# PowerManagement.net
KiCad netlist of a schematic drawn in Altium Designer
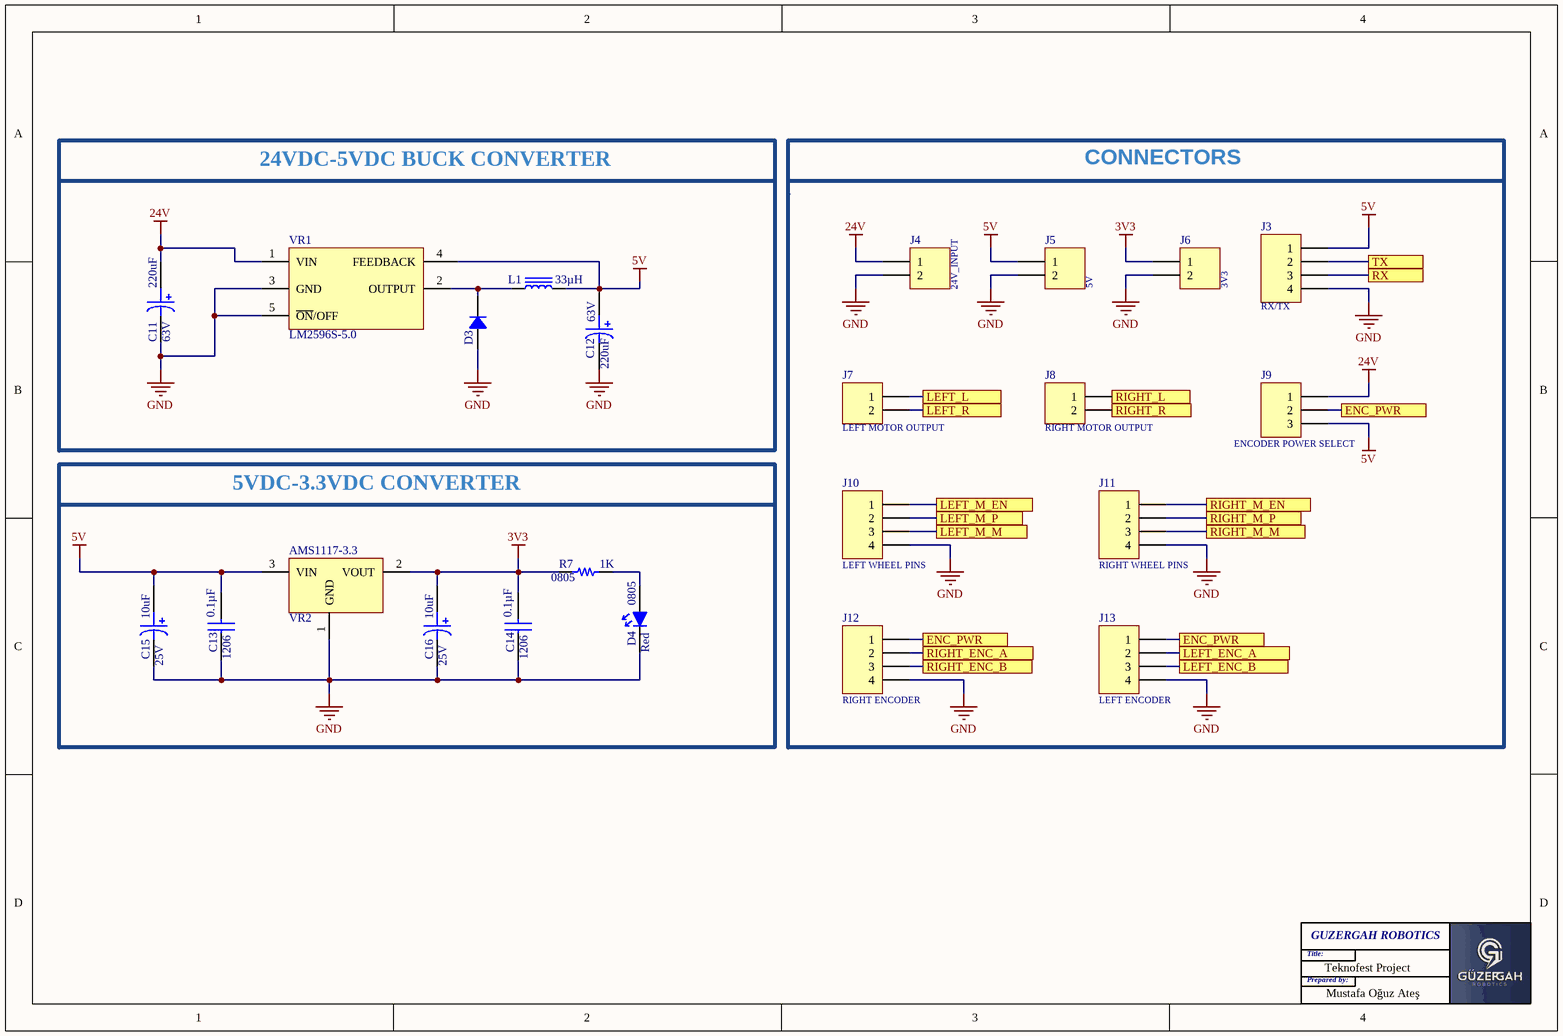
[diagram p0: PowerManagement.SchDoc]

(export (version "E")
  (design (tool "Eeschema 10.0.6"))
  (components
    (comp (ref "C11")
      (value "220uF")
      (footprint "CAP_ALUM_220uF_10x16 5MM")
      (description "CAP.EL.220uF 63V 10x16 5MM 105C")
      (fields (field (name "VOLTAGE - RATED") "63V") (field (name "Comment") "RD1J227M10016PA100"))
      (libsource (lib "TeknoFest") (part "CAP_ALUM_220uF_TH"))
    )
    (comp (ref "C12")
      (value "220uF")
      (footprint "CAP_ALUM_220uF_10x16 5MM")
      (description "CAP.EL.220uF 63V 10x16 5MM 105C")
      (fields (field (name "VOLTAGE - RATED") "63V") (field (name "Comment") "RD1J227M10016PA100"))
      (libsource (lib "TeknoFest") (part "CAP_ALUM_220uF_TH"))
    )
    (comp (ref "C13")
      (value "0.1µF")
      (footprint "CAP_1206_0.1uF")
      (description "CAP CER 0.1 uF 1206")
      (fields (field (name "PACKAGE / CASE") "1206") (field (name "Comment") "CAP_1206_0.1uF"))
      (libsource (lib "TeknoFest") (part "CAP_1206_0.1uF"))
    )
    (comp (ref "C14")
      (value "0.1µF")
      (footprint "CAP_1206_0.1uF")
      (description "CAP CER 0.1 uF 1206")
      (fields (field (name "PACKAGE / CASE") "1206") (field (name "Comment") "CAP_1206_0.1uF"))
      (libsource (lib "TeknoFest") (part "CAP_1206_0.1uF"))
    )
    (comp (ref "C15")
      (value "10uF")
      (footprint "CAP_ALUM_10uF_TH")
      (description "CAP.EL.10uF 25V 4x7 1.5MM 105C BULK KOSHIN")
      (fields (field (name "VOLTAGE - RATED") "25V") (field (name "Comment") "PKRJ-025V100MB070"))
      (libsource (lib "TeknoFest") (part "CAP_ALUM_10uF_TH"))
    )
    (comp (ref "C16")
      (value "10uF")
      (footprint "CAP_ALUM_10uF_TH")
      (description "CAP.EL.10uF 25V 4x7 1.5MM 105C BULK KOSHIN")
      (fields (field (name "VOLTAGE - RATED") "25V") (field (name "Comment") "PKRJ-025V100MB070"))
      (libsource (lib "TeknoFest") (part "CAP_ALUM_10uF_TH"))
    )
    (comp (ref "D3")
      (value "SK56-HT")
      (footprint "DIODE SCHOTTKY")
      (description "5A 60V DO214AB SMC")
      (libsource (lib "TeknoFest") (part "DIODE SCHOTTKY"))
    )
    (comp (ref "D4")
      (value "LED RED 0805")
      (footprint "LED_RED_0805")
      (description "KOMPONENT SEÇİLMEDİ")
      (fields
        (field (name "MANUFACTURER") "Osram Opto")
        (field (name "MANUFACTURER PART NUMBER") "LH R974-LP-1")
        (field (name "PACKAGE / CASE") "0805")
        (field (name "COLOR") "Red")
        (field (name "DESIGNED BY") "Mustafa")
      )
      (libsource (lib "TeknoFest") (part "LED RED 0805"))
    )
    (comp (ref "J3")
      (value "DS1023-1X4S21")
      (footprint "RX/TX HEADER")
      (description "FEMALE HEADER 4PIN(1x4) 2.54mm THT V/T TRAY")
      (libsource (lib "TeknoFest") (part "RX/TX HEADER"))
    )
    (comp (ref "J4")
      (value "DG381S-3.81-02P-14-00AH")
      (footprint "24V_IN KONNEKTÖR")
      (description "TERM.BLK.3.81MM 2P PCB TYPE GREEN")
      (libsource (lib "TeknoFest") (part "24V_IN"))
    )
    (comp (ref "J5")
      (value "L-KLS1-208-1-02-S")
      (footprint "5V JUMPER")
      (description "FEMALE HEADER 2PIN(1x2) 2.54mm THT V/T TRAY")
      (libsource (lib "TeknoFest") (part "5V_JUMPER_HEADER"))
    )
    (comp (ref "J6")
      (value "L-KLS1-208-1-02-S")
      (footprint "3V3 JUMPER")
      (description "FEMALE HEADER 2PIN(1x2) 2.54mm THT V/T TRAY")
      (libsource (lib "TeknoFest") (part "3V3_JUMPER_HEADER"))
    )
    (comp (ref "J7")
      (value "DG381S-3.81-02P-14-00AH")
      (footprint "LEFT MOTOR OUTPUT CONNECTOR")
      (description "DG381S-3.81-02P-14-00AH - TERM.BLK.3.81MM 2P PCB TYPE GREEN")
      (libsource (lib "TeknoFest") (part "LEFT MOTOR OUTPUT"))
    )
    (comp (ref "J8")
      (value "DG381S-3.81-02P-14-00AH")
      (footprint "RIGHT MOTOR OUTPUT CONNECTOR")
      (description "DG381S-3.81-02P-14-00AH - TERM.BLK.3.81MM 2P PCB TYPE GREEN")
      (libsource (lib "TeknoFest") (part "RIGHT MOTOR OUTPUT"))
    )
    (comp (ref "J9")
      (value "DS1023-1X3S21")
      (footprint "ENCODER POWER SELECT.1")
      (description "FEMALE HEADER 3PIN(1x3) 2.54mm THT V/T")
      (libsource (lib "TeknoFest") (part "ENCODER POWER SELECT"))
    )
    (comp (ref "J10")
      (value "DS1023-1X4S21")
      (footprint "LEFT WHEEL PINS")
      (description "FEMALE HEADER 4PIN(1x4) 2.54mm THT V/T TRAY")
      (libsource (lib "TeknoFest") (part "LEFT WHEEL PINS"))
    )
    (comp (ref "J11")
      (value "DS1023-1X4S21")
      (footprint "RIGHT WHEEL PINS")
      (description "DS1023-1X4S21 - FEMALE HEADER 4PIN(1x4) 2.54mm THT V/T TRAY")
      (libsource (lib "TeknoFest") (part "RIGHT WHEEL PINS"))
    )
    (comp (ref "J12")
      (value "15EDGA-3.81-04P-14-00AH")
      (footprint "RIGHT ENCODER")
      (description "TERM.BLK.3.81MM 4P FEMALE GREEN")
      (libsource (lib "TeknoFest") (part "RIGHT ENCODER"))
    )
    (comp (ref "J13")
      (value "15EDGA-3.81-04P-14-00AH")
      (footprint "LEFT ENCODER")
      (description "TERM.BLK.3.81MM 4P FEMALE GREEN KLEMENS")
      (libsource (lib "TeknoFest") (part "LEFT ENCODER"))
    )
    (comp (ref "L1")
      (value "33µH")
      (footprint "INDUCTOR POWER")
      (description "INDUCTOR POWER 33UH 3.5A SMD BOURNS")
      (fields (field (name "Comment") "SRR1280-330M"))
      (libsource (lib "TeknoFest") (part "INDUCTOR_POWER_33uH"))
    )
    (comp (ref "R7")
      (value "1K")
      (footprint "RES_0805_1K")
      (description "RES 0805 1K ohm")
      (fields (field (name "PACKAGE / CASE") "0805") (field (name "Comment") "RES_0805_1K"))
      (libsource (lib "TeknoFest") (part "RES_0805_1K"))
    )
    (comp (ref "VR1")
      (value "LM2596S-5.0")
      (footprint "TO263-5 (D2PAK)")
      (description "LM2596S-5.0 - IC-2596 REG BUCK 5V 3A TO263-5")
      (libsource (lib "TeknoFest") (part "LM2596S-5.0"))
    )
    (comp (ref "VR2")
      (value "AMS1117-3.3")
      (footprint "SOT-223")
      (description "IC-1117 V.REG. 1A 3V3 SOT223 SMD AMS")
      (fields
        (field (name "MANUFACTURER") "UMW(Youtai Semiconductor Co., Ltd.)")
        (field (name "DESIGNED BY") "Mustafa oğuz Ateş")
      )
      (libsource (lib "TeknoFest") (part "AMS1117-3.3"))
    )
  )
  (nets
    (net (code "1") (name "/ENC_PWR") (class "Default")
      (node (ref "J12") (pin "1") (pinfunction "1_1") (pintype "passive"))
      (node (ref "J13") (pin "1") (pinfunction "1_1") (pintype "passive"))
      (node (ref "J9") (pin "2") (pinfunction "2_2") (pintype "passive"))
    )
    (net (code "2") (name "/LEFT_ENC_A") (class "Default")
      (node (ref "J13") (pin "2") (pinfunction "2_2") (pintype "passive"))
    )
    (net (code "3") (name "/LEFT_ENC_B") (class "Default")
      (node (ref "J13") (pin "3") (pinfunction "3_3") (pintype "passive"))
    )
    (net (code "4") (name "/LEFT_L") (class "Default")
      (node (ref "J7") (pin "1") (pinfunction "1_1") (pintype "passive"))
    )
    (net (code "5") (name "/LEFT_M_EN") (class "Default")
      (node (ref "J10") (pin "1") (pinfunction "1_1") (pintype "passive"))
    )
    (net (code "6") (name "/LEFT_M_M") (class "Default")
      (node (ref "J10") (pin "3") (pinfunction "3_3") (pintype "passive"))
    )
    (net (code "7") (name "/LEFT_M_P") (class "Default")
      (node (ref "J10") (pin "2") (pinfunction "2_2") (pintype "passive"))
    )
    (net (code "8") (name "/LEFT_R") (class "Default")
      (node (ref "J7") (pin "2") (pinfunction "2_2") (pintype "passive"))
    )
    (net (code "9") (name "/RIGHT_ENC_A") (class "Default")
      (node (ref "J12") (pin "2") (pinfunction "2_2") (pintype "passive"))
    )
    (net (code "10") (name "/RIGHT_ENC_B") (class "Default")
      (node (ref "J12") (pin "3") (pinfunction "3_3") (pintype "passive"))
    )
    (net (code "11") (name "/RIGHT_L") (class "Default")
      (node (ref "J8") (pin "1") (pinfunction "1_1") (pintype "passive"))
    )
    (net (code "12") (name "/RIGHT_M_EN") (class "Default")
      (node (ref "J11") (pin "1") (pinfunction "1_1") (pintype "passive"))
    )
    (net (code "13") (name "/RIGHT_M_M") (class "Default")
      (node (ref "J11") (pin "3") (pinfunction "3_3") (pintype "passive"))
    )
    (net (code "14") (name "/RIGHT_M_P") (class "Default")
      (node (ref "J11") (pin "2") (pinfunction "2_2") (pintype "passive"))
    )
    (net (code "15") (name "/RIGHT_R") (class "Default")
      (node (ref "J8") (pin "2") (pinfunction "2_2") (pintype "passive"))
    )
    (net (code "16") (name "/RX") (class "Default")
      (node (ref "J3") (pin "3") (pinfunction "3_3") (pintype "passive"))
    )
    (net (code "17") (name "/TX") (class "Default")
      (node (ref "J3") (pin "2") (pinfunction "2_2") (pintype "passive"))
    )
    (net (code "18") (name "3V3") (class "Default")
      (node (ref "C14") (pin "2") (pinfunction "2_2") (pintype "passive"))
      (node (ref "C16") (pin "1") (pinfunction "1_1") (pintype "passive"))
      (node (ref "J6") (pin "1") (pinfunction "1_1") (pintype "passive"))
      (node (ref "R7") (pin "1") (pinfunction "1_1") (pintype "passive"))
      (node (ref "VR2") (pin "2") (pinfunction "VOUT_2") (pintype "passive"))
    )
    (net (code "19") (name "5V") (class "Default")
      (node (ref "C12") (pin "1") (pinfunction "1_1") (pintype "passive"))
      (node (ref "C13") (pin "2") (pinfunction "2_2") (pintype "passive"))
      (node (ref "C15") (pin "1") (pinfunction "1_1") (pintype "passive"))
      (node (ref "J3") (pin "1") (pinfunction "1_1") (pintype "passive"))
      (node (ref "J5") (pin "1") (pinfunction "1_1") (pintype "passive"))
      (node (ref "J9") (pin "3") (pinfunction "3_3") (pintype "passive"))
      (node (ref "L1") (pin "2") (pinfunction "2_2") (pintype "passive"))
      (node (ref "VR2") (pin "3") (pinfunction "VIN_3") (pintype "passive"))
    )
    (net (code "20") (name "24V") (class "Default")
      (node (ref "C11") (pin "1") (pinfunction "1_1") (pintype "passive"))
      (node (ref "J4") (pin "1") (pinfunction "1_1") (pintype "passive"))
      (node (ref "J9") (pin "1") (pinfunction "1_1") (pintype "passive"))
      (node (ref "VR1") (pin "1") (pinfunction "VIN_1") (pintype "passive"))
    )
    (net (code "21") (name "GND") (class "Default")
      (node (ref "C11") (pin "2") (pinfunction "2_2") (pintype "passive"))
      (node (ref "C12") (pin "2") (pinfunction "2_2") (pintype "passive"))
      (node (ref "C13") (pin "1") (pinfunction "1_1") (pintype "passive"))
      (node (ref "C14") (pin "1") (pinfunction "1_1") (pintype "passive"))
      (node (ref "C15") (pin "2") (pinfunction "2_2") (pintype "passive"))
      (node (ref "C16") (pin "2") (pinfunction "2_2") (pintype "passive"))
      (node (ref "D3") (pin "2") (pinfunction "2_2") (pintype "passive"))
      (node (ref "D4") (pin "1") (pinfunction "1_1") (pintype "power_in"))
      (node (ref "J10") (pin "4") (pinfunction "4_4") (pintype "passive"))
      (node (ref "J11") (pin "4") (pinfunction "4_4") (pintype "passive"))
      (node (ref "J12") (pin "4") (pinfunction "4_4") (pintype "passive"))
      (node (ref "J13") (pin "4") (pinfunction "4_4") (pintype "passive"))
      (node (ref "J3") (pin "4") (pinfunction "4_4") (pintype "passive"))
      (node (ref "J4") (pin "2") (pinfunction "2_2") (pintype "passive"))
      (node (ref "J5") (pin "2") (pinfunction "2_2") (pintype "passive"))
      (node (ref "J6") (pin "2") (pinfunction "2_2") (pintype "passive"))
      (node (ref "VR1") (pin "3") (pinfunction "GND_3") (pintype "passive"))
      (node (ref "VR1") (pin "5") (pinfunction "~{ON}/OFF_5") (pintype "passive"))
      (node (ref "VR2") (pin "1") (pinfunction "GND_1") (pintype "passive"))
    )
    (net (code "22") (name "Net-(D4-Pad2)") (class "Default")
      (node (ref "D4") (pin "2") (pinfunction "2_2") (pintype "power_in"))
      (node (ref "R7") (pin "2") (pinfunction "2_2") (pintype "passive"))
    )
    (net (code "23") (name "Net-(VR1-OUTPUT)") (class "Default")
      (node (ref "D3") (pin "1") (pinfunction "2_1") (pintype "passive"))
      (node (ref "L1") (pin "1") (pinfunction "1_1") (pintype "passive"))
      (node (ref "VR1") (pin "2") (pinfunction "OUTPUT_2") (pintype "passive"))
    )
    (net (code "24") (name "unconnected-(VR1-FEEDBACK-Pad4)") (class "Default")
      (node (ref "VR1") (pin "4") (pinfunction "FEEDBACK_4") (pintype "passive"))
    )
  )
)
